# internal_excitation-_7.net
KiCad netlist of a schematic drawn in EAGLE
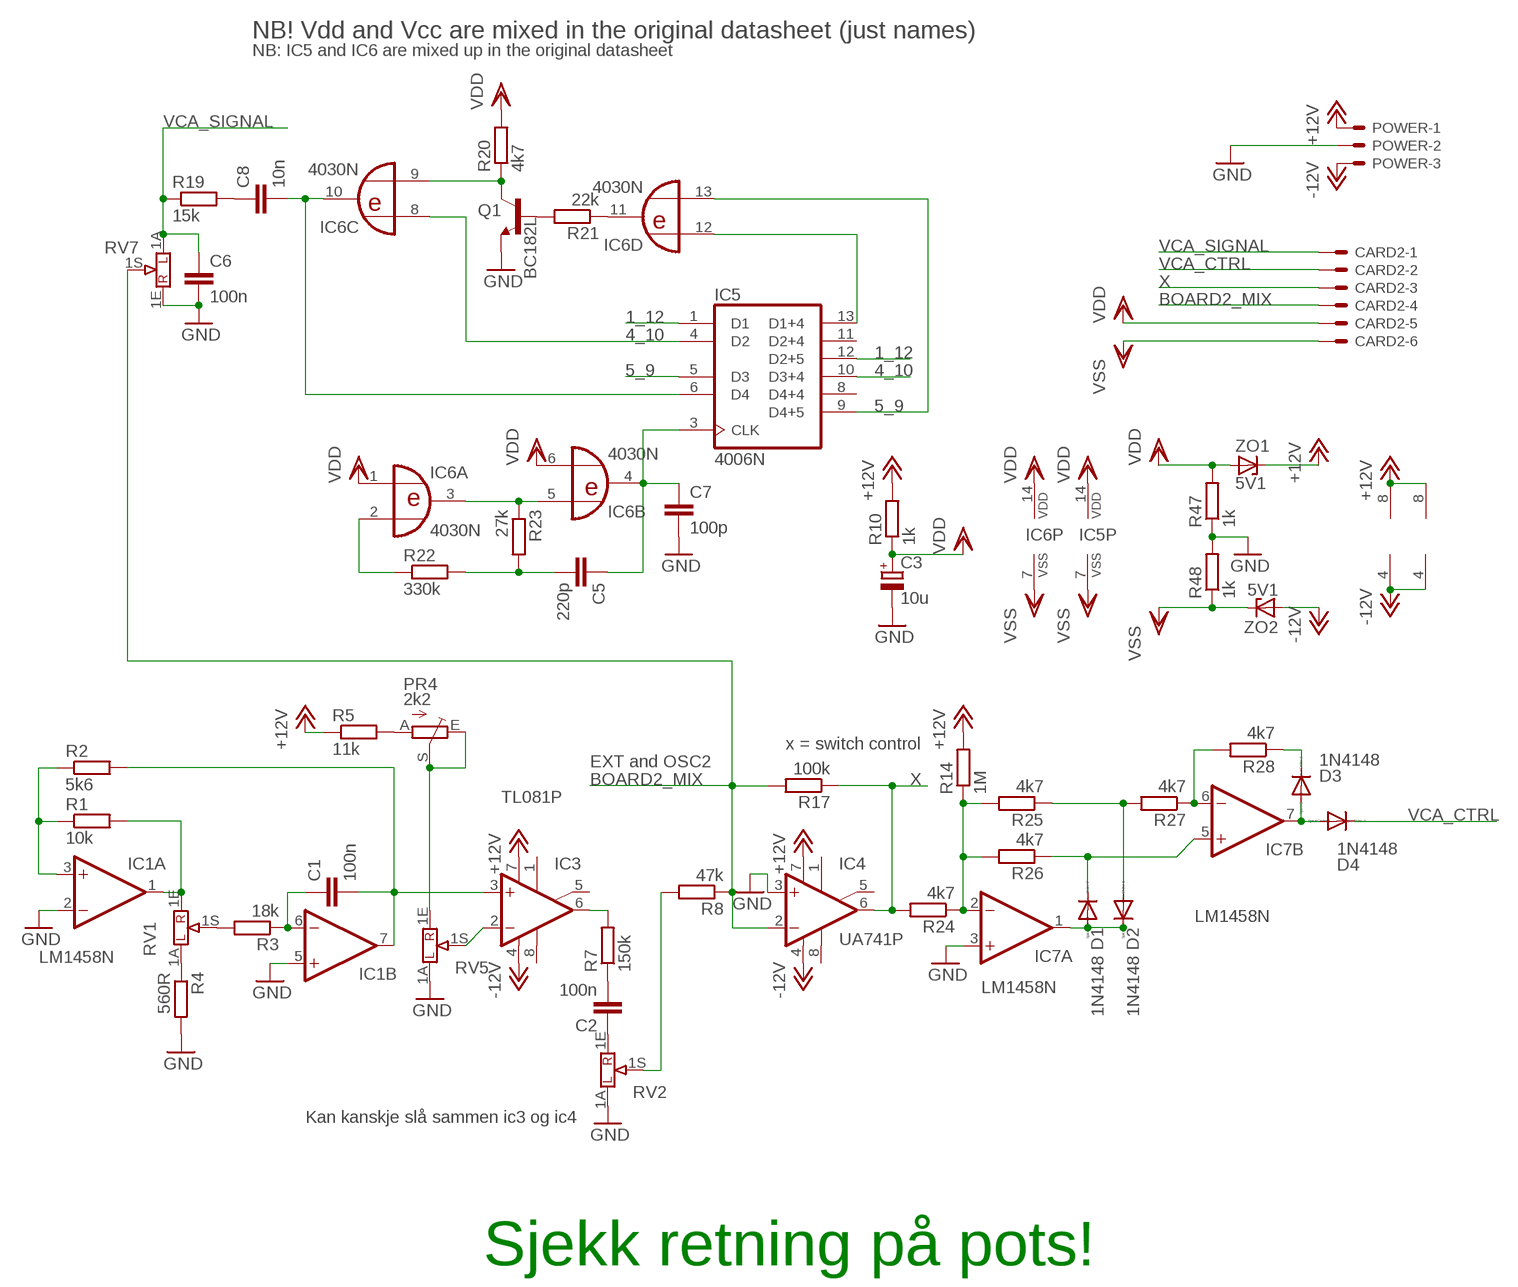
[diagram p0: schematic, sheet 1]

(export (version "E")
  (design (tool "Eeschema 10.0.6"))
  (components
    (comp (ref "C1")
      (value "100n")
      (footprint "eagle-import:C050-025X075")
      (libsource (lib "eagle-import") (part "C-EU050-025X075"))
    )
    (comp (ref "C2")
      (value "100n")
      (footprint "eagle-import:C025-025X050")
      (libsource (lib "eagle-import") (part "C-EU025-025X050"))
    )
    (comp (ref "C3")
      (value "10u")
      (footprint "eagle-import:E2,5-5")
      (libsource (lib "eagle-import") (part "CPOL-EUE2.5-5"))
    )
    (comp (ref "C5")
      (value "220p")
      (footprint "eagle-import:C025-025X050")
      (libsource (lib "eagle-import") (part "C-EU025-025X050"))
    )
    (comp (ref "C6")
      (value "100n")
      (footprint "eagle-import:C025-025X050")
      (libsource (lib "eagle-import") (part "C-EU025-025X050"))
    )
    (comp (ref "C7")
      (value "100p")
      (footprint "eagle-import:C025-025X050")
      (libsource (lib "eagle-import") (part "C-EU025-025X050"))
    )
    (comp (ref "C8")
      (value "10n")
      (footprint "eagle-import:C050-025X075")
      (libsource (lib "eagle-import") (part "C-EU050-025X075"))
    )
    (comp (ref "CARD2")
      (value "22-23-2061")
      (footprint "eagle-import:22-23-2061")
      (fields (field (name "MF") "MOLEX"))
      (libsource (lib "eagle-import") (part "22-23-2061"))
    )
    (comp (ref "D1")
      (value "1N4148")
      (footprint "eagle-import:DO35-5J")
      (libsource (lib "eagle-import") (part "1N4148DOJ35-5"))
    )
    (comp (ref "D2")
      (value "1N4148")
      (footprint "eagle-import:DO35-5J")
      (libsource (lib "eagle-import") (part "1N4148DOJ35-5"))
    )
    (comp (ref "D3")
      (value "1N4148")
      (footprint "eagle-import:DO35-5J")
      (libsource (lib "eagle-import") (part "1N4148DOJ35-5"))
    )
    (comp (ref "D4")
      (value "1N4148")
      (footprint "eagle-import:DO35-5J")
      (libsource (lib "eagle-import") (part "1N4148DOJ35-5"))
    )
    (comp (ref "IC1")
      (value "LM1458N")
      (footprint "eagle-import:DIL08")
      (libsource (lib "eagle-import") (part "1458NLM"))
    )
    (comp (ref "IC3")
      (value "TL081P")
      (footprint "eagle-import:DIL08")
      (libsource (lib "eagle-import") (part "TL081P"))
    )
    (comp (ref "IC4")
      (value "UA741P")
      (footprint "eagle-import:DIL08")
      (libsource (lib "eagle-import") (part "741PUA"))
    )
    (comp (ref "IC5")
      (value "4006N")
      (footprint "eagle-import:DIL14")
      (libsource (lib "eagle-import") (part "4006N"))
    )
    (comp (ref "IC6")
      (value "4030N")
      (footprint "eagle-import:DIL14")
      (libsource (lib "eagle-import") (part "4030N"))
    )
    (comp (ref "IC7")
      (value "LM1458N")
      (footprint "eagle-import:DIL08")
      (libsource (lib "eagle-import") (part "1458NLM"))
    )
    (comp (ref "POWER")
      (value "KK-156-3")
      (footprint "eagle-import:KK-156-3")
      (libsource (lib "eagle-import") (part "KK-156-3"))
    )
    (comp (ref "PR4")
      (value "2k2")
      (footprint "eagle-import:CA9V")
      (libsource (lib "eagle-import") (part "TRIM_EU-CA9V"))
    )
    (comp (ref "Q1")
      (value "BC182L")
      (footprint "eagle-import:TO92-ECB")
      (libsource (lib "eagle-import") (part "-NPN-TO92-ECB"))
    )
    (comp (ref "R1")
      (value "10k")
      (footprint "eagle-import:0207_7")
      (libsource (lib "eagle-import") (part "R-EU_0207/7"))
    )
    (comp (ref "R2")
      (value "5k6")
      (footprint "eagle-import:0207_7")
      (libsource (lib "eagle-import") (part "R-EU_0207/7"))
    )
    (comp (ref "R3")
      (value "18k")
      (footprint "eagle-import:0207_7")
      (libsource (lib "eagle-import") (part "R-EU_0207/7"))
    )
    (comp (ref "R4")
      (value "560R")
      (footprint "eagle-import:0207_7")
      (libsource (lib "eagle-import") (part "R-EU_0207/7"))
    )
    (comp (ref "R5")
      (value "11k")
      (footprint "eagle-import:0207_7")
      (libsource (lib "eagle-import") (part "R-EU_0207/7"))
    )
    (comp (ref "R7")
      (value "150k")
      (footprint "eagle-import:0207_7")
      (libsource (lib "eagle-import") (part "R-EU_0207/7"))
    )
    (comp (ref "R8")
      (value "47k")
      (footprint "eagle-import:0207_7")
      (libsource (lib "eagle-import") (part "R-EU_0207/7"))
    )
    (comp (ref "R10")
      (value "1k")
      (footprint "eagle-import:0207_7")
      (libsource (lib "eagle-import") (part "R-EU_0207/7"))
    )
    (comp (ref "R14")
      (value "1M")
      (footprint "eagle-import:0207_7")
      (libsource (lib "eagle-import") (part "R-EU_0207/7"))
    )
    (comp (ref "R17")
      (value "100k")
      (footprint "eagle-import:0207_7")
      (libsource (lib "eagle-import") (part "R-EU_0207/7"))
    )
    (comp (ref "R19")
      (value "15k")
      (footprint "eagle-import:0207_7")
      (libsource (lib "eagle-import") (part "R-EU_0207/7"))
    )
    (comp (ref "R20")
      (value "4k7")
      (footprint "eagle-import:0207_7")
      (libsource (lib "eagle-import") (part "R-EU_0207/7"))
    )
    (comp (ref "R21")
      (value "22k")
      (footprint "eagle-import:0207_7")
      (libsource (lib "eagle-import") (part "R-EU_0207/7"))
    )
    (comp (ref "R22")
      (value "330k")
      (footprint "eagle-import:0207_7")
      (libsource (lib "eagle-import") (part "R-EU_0207/7"))
    )
    (comp (ref "R23")
      (value "27k")
      (footprint "eagle-import:0207_7")
      (libsource (lib "eagle-import") (part "R-EU_0207/7"))
    )
    (comp (ref "R24")
      (value "4k7")
      (footprint "eagle-import:0207_7")
      (libsource (lib "eagle-import") (part "R-EU_0207/7"))
    )
    (comp (ref "R25")
      (value "4k7")
      (footprint "eagle-import:0207_7")
      (libsource (lib "eagle-import") (part "R-EU_0207/7"))
    )
    (comp (ref "R26")
      (value "4k7")
      (footprint "eagle-import:0207_7")
      (libsource (lib "eagle-import") (part "R-EU_0207/7"))
    )
    (comp (ref "R27")
      (value "4k7")
      (footprint "eagle-import:0207_7")
      (libsource (lib "eagle-import") (part "R-EU_0207/7"))
    )
    (comp (ref "R28")
      (value "4k7")
      (footprint "eagle-import:0207_7")
      (libsource (lib "eagle-import") (part "R-EU_0207/7"))
    )
    (comp (ref "R47")
      (value "1k")
      (footprint "eagle-import:0207_7")
      (libsource (lib "eagle-import") (part "R-EU_0207/7"))
    )
    (comp (ref "R48")
      (value "1k")
      (footprint "eagle-import:0207_7")
      (libsource (lib "eagle-import") (part "R-EU_0207/7"))
    )
    (comp (ref "RV1")
      (value "10k log")
      (footprint "eagle-import:POT16_W_BRACKET")
      (libsource (lib "eagle-import") (part "POT16_W_BRACKET{dblquote}{dblquote}"))
    )
    (comp (ref "RV2")
      (value "10k log")
      (footprint "eagle-import:POT16_W_BRACKET")
      (libsource (lib "eagle-import") (part "POT16_W_BRACKET{dblquote}{dblquote}"))
    )
    (comp (ref "RV5")
      (value "10k")
      (footprint "eagle-import:POT16_W_BRACKET")
      (libsource (lib "eagle-import") (part "POT16_W_BRACKET{dblquote}{dblquote}"))
    )
    (comp (ref "RV7")
      (value "10k")
      (footprint "eagle-import:POT16_W_BRACKET")
      (libsource (lib "eagle-import") (part "POT16_W_BRACKET{dblquote}{dblquote}"))
    )
    (comp (ref "ZO1")
      (value "5V1")
      (footprint "eagle-import:ZDIO-5")
      (libsource (lib "eagle-import") (part "ZENER-DIODEZD-5"))
    )
    (comp (ref "ZO2")
      (value "5V1")
      (footprint "eagle-import:ZDIO-5")
      (libsource (lib "eagle-import") (part "ZENER-DIODEZD-5"))
    )
  )
  (nets
    (net (code "1") (name "+12V") (class "Default")
      (node (ref "IC1") (pin "8") (pinfunction "V+_8") (pintype "power_in"))
      (node (ref "IC3") (pin "7") (pinfunction "V+_7") (pintype "power_in"))
      (node (ref "IC4") (pin "7") (pinfunction "V+_7") (pintype "power_in"))
      (node (ref "IC7") (pin "8") (pinfunction "V+_8") (pintype "power_in"))
      (node (ref "POWER") (pin "1") (pinfunction "S_1") (pintype "passive"))
      (node (ref "R10") (pin "2") (pinfunction "2_2") (pintype "passive"))
      (node (ref "R14") (pin "2") (pinfunction "2_2") (pintype "passive"))
      (node (ref "R5") (pin "1") (pinfunction "1_1") (pintype "passive"))
      (node (ref "ZO1") (pin "C") (pinfunction "C_C") (pintype "passive"))
    )
    (net (code "2") (name "-12V") (class "Default")
      (node (ref "IC1") (pin "4") (pinfunction "V-_4") (pintype "power_in"))
      (node (ref "IC3") (pin "4") (pinfunction "V-_4") (pintype "power_in"))
      (node (ref "IC4") (pin "4") (pinfunction "V-_4") (pintype "power_in"))
      (node (ref "IC7") (pin "4") (pinfunction "V-_4") (pintype "power_in"))
      (node (ref "POWER") (pin "3") (pinfunction "S_3") (pintype "passive"))
      (node (ref "ZO2") (pin "A") (pinfunction "A_A") (pintype "passive"))
    )
    (net (code "3") (name "/1_12") (class "Default")
      (node (ref "IC5") (pin "1") (pinfunction "D1_1") (pintype "input"))
      (node (ref "IC5") (pin "12") (pinfunction "D2+5_12") (pintype "output"))
    )
    (net (code "4") (name "/4_10") (class "Default")
      (node (ref "IC5") (pin "10") (pinfunction "D3+4_10") (pintype "output"))
      (node (ref "IC5") (pin "4") (pinfunction "D2_4") (pintype "input"))
      (node (ref "IC6") (pin "8") (pinfunction "I0_8") (pintype "input"))
    )
    (net (code "5") (name "/5_9") (class "Default")
      (node (ref "IC5") (pin "5") (pinfunction "D3_5") (pintype "input"))
      (node (ref "IC5") (pin "9") (pinfunction "D4+5_9") (pintype "output"))
      (node (ref "IC6") (pin "13") (pinfunction "I1_13") (pintype "input"))
    )
    (net (code "6") (name "/BOARD2_MIX") (class "Default")
      (node (ref "CARD2") (pin "4") (pinfunction "S_4") (pintype "passive"))
      (node (ref "IC4") (pin "2") (pinfunction "-IN_2") (pintype "input"))
      (node (ref "R17") (pin "2") (pinfunction "2_2") (pintype "passive"))
      (node (ref "R8") (pin "1") (pinfunction "1_1") (pintype "passive"))
      (node (ref "RV7") (pin "1S") (pinfunction "1S_1S") (pintype "passive"))
    )
    (net (code "7") (name "/VCA_CTRL") (class "Default")
      (node (ref "CARD2") (pin "2") (pinfunction "S_2") (pintype "passive"))
      (node (ref "D4") (pin "C") (pinfunction "C_C") (pintype "passive"))
    )
    (net (code "8") (name "/VCA_SIGNAL") (class "Default")
      (node (ref "C6") (pin "1") (pinfunction "1_1") (pintype "passive"))
      (node (ref "CARD2") (pin "1") (pinfunction "S_1") (pintype "passive"))
      (node (ref "R19") (pin "1") (pinfunction "1_1") (pintype "passive"))
      (node (ref "RV7") (pin "1A") (pinfunction "1A_1A") (pintype "passive"))
    )
    (net (code "9") (name "/X") (class "Default")
      (node (ref "CARD2") (pin "3") (pinfunction "S_3") (pintype "passive"))
      (node (ref "IC4") (pin "6") (pinfunction "OUT_6") (pintype "output"))
      (node (ref "R17") (pin "1") (pinfunction "1_1") (pintype "passive"))
      (node (ref "R24") (pin "2") (pinfunction "2_2") (pintype "passive"))
    )
    (net (code "10") (name "GND") (class "Default")
      (node (ref "C3") (pin "-") (pinfunction "-_-") (pintype "passive"))
      (node (ref "C6") (pin "2") (pinfunction "2_2") (pintype "passive"))
      (node (ref "C7") (pin "2") (pinfunction "2_2") (pintype "passive"))
      (node (ref "IC1") (pin "2") (pinfunction "-IN_2") (pintype "input"))
      (node (ref "IC1") (pin "5") (pinfunction "+IN_5") (pintype "input"))
      (node (ref "IC4") (pin "3") (pinfunction "+IN_3") (pintype "input"))
      (node (ref "IC7") (pin "3") (pinfunction "+IN_3") (pintype "input"))
      (node (ref "POWER") (pin "2") (pinfunction "S_2") (pintype "passive"))
      (node (ref "Q1") (pin "E") (pinfunction "E_E") (pintype "passive"))
      (node (ref "R4") (pin "2") (pinfunction "2_2") (pintype "passive"))
      (node (ref "R47") (pin "1") (pinfunction "1_1") (pintype "passive"))
      (node (ref "R48") (pin "2") (pinfunction "2_2") (pintype "passive"))
      (node (ref "RV2") (pin "1A") (pinfunction "1A_1A") (pintype "passive"))
      (node (ref "RV5") (pin "1A") (pinfunction "1A_1A") (pintype "passive"))
      (node (ref "RV7") (pin "1E") (pinfunction "1E_1E") (pintype "passive"))
    )
    (net (code "11") (name "Net-(C2-Pad1)") (class "Default")
      (node (ref "C2") (pin "1") (pinfunction "1_1") (pintype "passive"))
      (node (ref "RV2") (pin "1E") (pinfunction "1E_1E") (pintype "passive"))
    )
    (net (code "12") (name "Net-(C2-Pad2)") (class "Default")
      (node (ref "C2") (pin "2") (pinfunction "2_2") (pintype "passive"))
      (node (ref "R7") (pin "1") (pinfunction "1_1") (pintype "passive"))
    )
    (net (code "13") (name "Net-(C5-Pad2)") (class "Default")
      (node (ref "C5") (pin "2") (pinfunction "2_2") (pintype "passive"))
      (node (ref "R22") (pin "2") (pinfunction "2_2") (pintype "passive"))
      (node (ref "R23") (pin "2") (pinfunction "2_2") (pintype "passive"))
    )
    (net (code "14") (name "Net-(C8-Pad1)") (class "Default")
      (node (ref "C8") (pin "1") (pinfunction "1_1") (pintype "passive"))
      (node (ref "R19") (pin "2") (pinfunction "2_2") (pintype "passive"))
    )
    (net (code "15") (name "Net-(D2-PadA)") (class "Default")
      (node (ref "D2") (pin "A") (pinfunction "A_A") (pintype "passive"))
      (node (ref "R25") (pin "1") (pinfunction "1_1") (pintype "passive"))
      (node (ref "R27") (pin "2") (pinfunction "2_2") (pintype "passive"))
    )
    (net (code "16") (name "Net-(D3-PadC)") (class "Default")
      (node (ref "D3") (pin "C") (pinfunction "C_C") (pintype "passive"))
      (node (ref "R28") (pin "1") (pinfunction "1_1") (pintype "passive"))
    )
    (net (code "17") (name "Net-(IC1A-+IN)") (class "Default")
      (node (ref "IC1") (pin "3") (pinfunction "+IN_3") (pintype "input"))
      (node (ref "R1") (pin "1") (pinfunction "1_1") (pintype "passive"))
      (node (ref "R2") (pin "1") (pinfunction "1_1") (pintype "passive"))
    )
    (net (code "18") (name "Net-(IC1A-OUT)") (class "Default")
      (node (ref "IC1") (pin "1") (pinfunction "OUT_1") (pintype "output"))
      (node (ref "R1") (pin "2") (pinfunction "2_2") (pintype "passive"))
      (node (ref "RV1") (pin "1E") (pinfunction "1E_1E") (pintype "passive"))
    )
    (net (code "19") (name "Net-(IC1B--IN)") (class "Default")
      (node (ref "C1") (pin "1") (pinfunction "1_1") (pintype "passive"))
      (node (ref "IC1") (pin "6") (pinfunction "-IN_6") (pintype "input"))
      (node (ref "R3") (pin "1") (pinfunction "1_1") (pintype "passive"))
    )
    (net (code "20") (name "Net-(IC1B-OUT)") (class "Default")
      (node (ref "C1") (pin "2") (pinfunction "2_2") (pintype "passive"))
      (node (ref "IC1") (pin "7") (pinfunction "OUT_7") (pintype "output"))
      (node (ref "IC3") (pin "3") (pinfunction "+IN_3") (pintype "input"))
      (node (ref "R2") (pin "2") (pinfunction "2_2") (pintype "passive"))
    )
    (net (code "21") (name "Net-(IC3--IN)") (class "Default")
      (node (ref "IC3") (pin "2") (pinfunction "-IN_2") (pintype "input"))
      (node (ref "RV5") (pin "1S") (pinfunction "1S_1S") (pintype "passive"))
    )
    (net (code "22") (name "Net-(IC3-OUT)") (class "Default")
      (node (ref "IC3") (pin "6") (pinfunction "OUT_6") (pintype "output"))
      (node (ref "R7") (pin "2") (pinfunction "2_2") (pintype "passive"))
    )
    (net (code "23") (name "Net-(IC5A-CLK)") (class "Default")
      (node (ref "C5") (pin "1") (pinfunction "1_1") (pintype "passive"))
      (node (ref "C7") (pin "1") (pinfunction "1_1") (pintype "passive"))
      (node (ref "IC5") (pin "3") (pinfunction "CLK_3") (pintype "input"))
      (node (ref "IC6") (pin "4") (pinfunction "O_4") (pintype "output"))
    )
    (net (code "24") (name "Net-(IC5A-D1+4)") (class "Default")
      (node (ref "IC5") (pin "13") (pinfunction "D1+4_13") (pintype "output"))
      (node (ref "IC6") (pin "12") (pinfunction "I0_12") (pintype "input"))
    )
    (net (code "25") (name "Net-(IC5A-D4)") (class "Default")
      (node (ref "C8") (pin "2") (pinfunction "2_2") (pintype "passive"))
      (node (ref "IC5") (pin "6") (pinfunction "D4_6") (pintype "input"))
      (node (ref "IC6") (pin "10") (pinfunction "O_10") (pintype "output"))
    )
    (net (code "26") (name "Net-(IC6A-I1)") (class "Default")
      (node (ref "IC6") (pin "2") (pinfunction "I1_2") (pintype "input"))
      (node (ref "R22") (pin "1") (pinfunction "1_1") (pintype "passive"))
    )
    (net (code "27") (name "Net-(IC6A-O)") (class "Default")
      (node (ref "IC6") (pin "3") (pinfunction "O_3") (pintype "output"))
      (node (ref "IC6") (pin "5") (pinfunction "I0_5") (pintype "input"))
      (node (ref "R23") (pin "1") (pinfunction "1_1") (pintype "passive"))
    )
    (net (code "28") (name "Net-(IC6C-I1)") (class "Default")
      (node (ref "IC6") (pin "9") (pinfunction "I1_9") (pintype "input"))
      (node (ref "Q1") (pin "C") (pinfunction "C_C") (pintype "passive"))
      (node (ref "R20") (pin "1") (pinfunction "1_1") (pintype "passive"))
    )
    (net (code "29") (name "Net-(IC6D-O)") (class "Default")
      (node (ref "IC6") (pin "11") (pinfunction "O_11") (pintype "output"))
      (node (ref "R21") (pin "1") (pinfunction "1_1") (pintype "passive"))
    )
    (net (code "30") (name "Net-(IC7A--IN)") (class "Default")
      (node (ref "IC7") (pin "2") (pinfunction "-IN_2") (pintype "input"))
      (node (ref "R14") (pin "1") (pinfunction "1_1") (pintype "passive"))
      (node (ref "R24") (pin "1") (pinfunction "1_1") (pintype "passive"))
      (node (ref "R25") (pin "2") (pinfunction "2_2") (pintype "passive"))
      (node (ref "R26") (pin "2") (pinfunction "2_2") (pintype "passive"))
    )
    (net (code "31") (name "Net-(IC7A-OUT)") (class "Default")
      (node (ref "D1") (pin "A") (pinfunction "A_A") (pintype "passive"))
      (node (ref "D2") (pin "C") (pinfunction "C_C") (pintype "passive"))
      (node (ref "IC7") (pin "1") (pinfunction "OUT_1") (pintype "output"))
    )
    (net (code "32") (name "Net-(IC7B-+IN)") (class "Default")
      (node (ref "D1") (pin "C") (pinfunction "C_C") (pintype "passive"))
      (node (ref "IC7") (pin "5") (pinfunction "+IN_5") (pintype "input"))
      (node (ref "R26") (pin "1") (pinfunction "1_1") (pintype "passive"))
    )
    (net (code "33") (name "Net-(IC7B--IN)") (class "Default")
      (node (ref "IC7") (pin "6") (pinfunction "-IN_6") (pintype "input"))
      (node (ref "R27") (pin "1") (pinfunction "1_1") (pintype "passive"))
      (node (ref "R28") (pin "2") (pinfunction "2_2") (pintype "passive"))
    )
    (net (code "34") (name "Net-(IC7B-OUT)") (class "Default")
      (node (ref "D3") (pin "A") (pinfunction "A_A") (pintype "passive"))
      (node (ref "D4") (pin "A") (pinfunction "A_A") (pintype "passive"))
      (node (ref "IC7") (pin "7") (pinfunction "OUT_7") (pintype "output"))
    )
    (net (code "35") (name "Net-(PR4-PadA)") (class "Default")
      (node (ref "PR4") (pin "A") (pinfunction "A_A") (pintype "passive"))
      (node (ref "R5") (pin "2") (pinfunction "2_2") (pintype "passive"))
    )
    (net (code "36") (name "Net-(PR4-PadE)") (class "Default")
      (node (ref "PR4") (pin "E") (pinfunction "E_E") (pintype "passive"))
      (node (ref "PR4") (pin "S") (pinfunction "S_S") (pintype "passive"))
      (node (ref "RV5") (pin "1E") (pinfunction "1E_1E") (pintype "passive"))
    )
    (net (code "37") (name "Net-(Q1-PadB)") (class "Default")
      (node (ref "Q1") (pin "B") (pinfunction "B_B") (pintype "passive"))
      (node (ref "R21") (pin "2") (pinfunction "2_2") (pintype "passive"))
    )
    (net (code "38") (name "Net-(R3-Pad2)") (class "Default")
      (node (ref "R3") (pin "2") (pinfunction "2_2") (pintype "passive"))
      (node (ref "RV1") (pin "1S") (pinfunction "1S_1S") (pintype "passive"))
    )
    (net (code "39") (name "Net-(R4-Pad1)") (class "Default")
      (node (ref "R4") (pin "1") (pinfunction "1_1") (pintype "passive"))
      (node (ref "RV1") (pin "1A") (pinfunction "1A_1A") (pintype "passive"))
    )
    (net (code "40") (name "Net-(R8-Pad2)") (class "Default")
      (node (ref "R8") (pin "2") (pinfunction "2_2") (pintype "passive"))
      (node (ref "RV2") (pin "1S") (pinfunction "1S_1S") (pintype "passive"))
    )
    (net (code "41") (name "VDD") (class "Default")
      (node (ref "C3") (pin "+") (pinfunction "+_+") (pintype "passive"))
      (node (ref "CARD2") (pin "5") (pinfunction "S_5") (pintype "passive"))
      (node (ref "IC5") (pin "14") (pinfunction "VDD_14") (pintype "power_in"))
      (node (ref "IC6") (pin "1") (pinfunction "I0_1") (pintype "input"))
      (node (ref "IC6") (pin "14") (pinfunction "VDD_14") (pintype "power_in"))
      (node (ref "IC6") (pin "6") (pinfunction "I1_6") (pintype "input"))
      (node (ref "R10") (pin "1") (pinfunction "1_1") (pintype "passive"))
      (node (ref "R20") (pin "2") (pinfunction "2_2") (pintype "passive"))
      (node (ref "R47") (pin "2") (pinfunction "2_2") (pintype "passive"))
      (node (ref "ZO1") (pin "A") (pinfunction "A_A") (pintype "passive"))
    )
    (net (code "42") (name "VSS") (class "Default")
      (node (ref "CARD2") (pin "6") (pinfunction "S_6") (pintype "passive"))
      (node (ref "IC5") (pin "7") (pinfunction "VSS_7") (pintype "power_in"))
      (node (ref "IC6") (pin "7") (pinfunction "VSS_7") (pintype "power_in"))
      (node (ref "R48") (pin "1") (pinfunction "1_1") (pintype "passive"))
      (node (ref "ZO2") (pin "C") (pinfunction "C_C") (pintype "passive"))
    )
    (net (code "43") (name "unconnected-(IC3-ON1-Pad1)") (class "Default")
      (node (ref "IC3") (pin "1") (pinfunction "ON1_1") (pintype "passive"))
    )
    (net (code "44") (name "unconnected-(IC3-ON2-Pad5)") (class "Default")
      (node (ref "IC3") (pin "5") (pinfunction "ON2_5") (pintype "passive"))
    )
    (net (code "45") (name "unconnected-(IC3-OPT-Pad8)") (class "Default")
      (node (ref "IC3") (pin "8") (pinfunction "OPT_8") (pintype "passive"))
    )
    (net (code "46") (name "unconnected-(IC4-ON1-Pad1)") (class "Default")
      (node (ref "IC4") (pin "1") (pinfunction "ON1_1") (pintype "passive"))
    )
    (net (code "47") (name "unconnected-(IC4-ON2-Pad5)") (class "Default")
      (node (ref "IC4") (pin "5") (pinfunction "ON2_5") (pintype "passive"))
    )
    (net (code "48") (name "unconnected-(IC4-OPT-Pad8)") (class "Default")
      (node (ref "IC4") (pin "8") (pinfunction "OPT_8") (pintype "passive"))
    )
    (net (code "49") (name "unconnected-(IC5A-D2+4-Pad11)") (class "Default")
      (node (ref "IC5") (pin "11") (pinfunction "D2+4_11") (pintype "output"))
    )
    (net (code "50") (name "unconnected-(IC5A-D4+4-Pad8)") (class "Default")
      (node (ref "IC5") (pin "8") (pinfunction "D4+4_8") (pintype "output"))
    )
  )
)
